# PDP8S.net
KiCad netlist of a schematic drawn in EAGLE
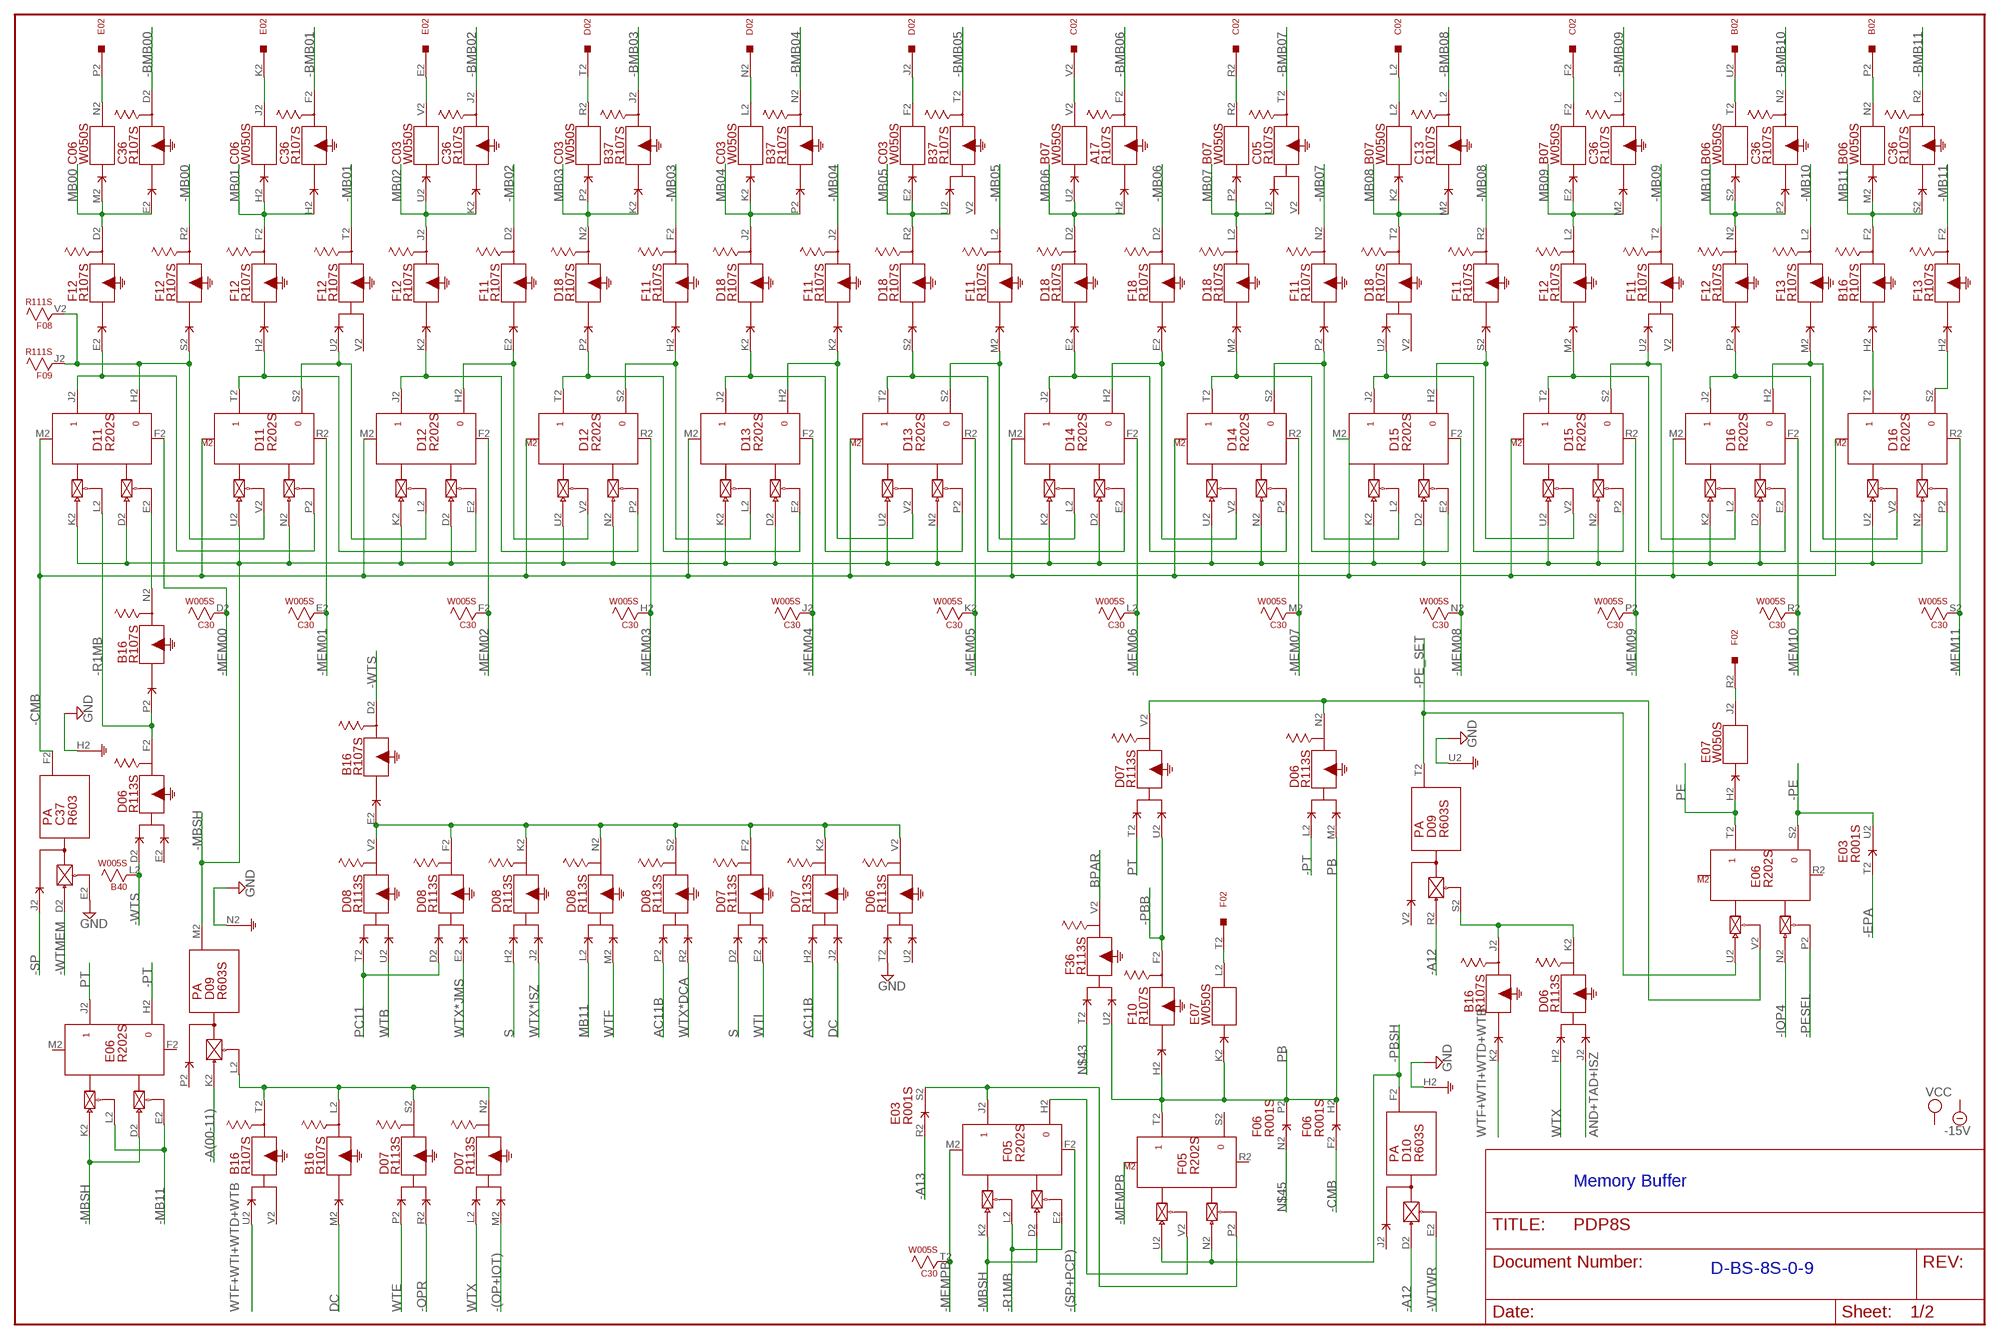
[diagram p0: schematic, sheet 1]
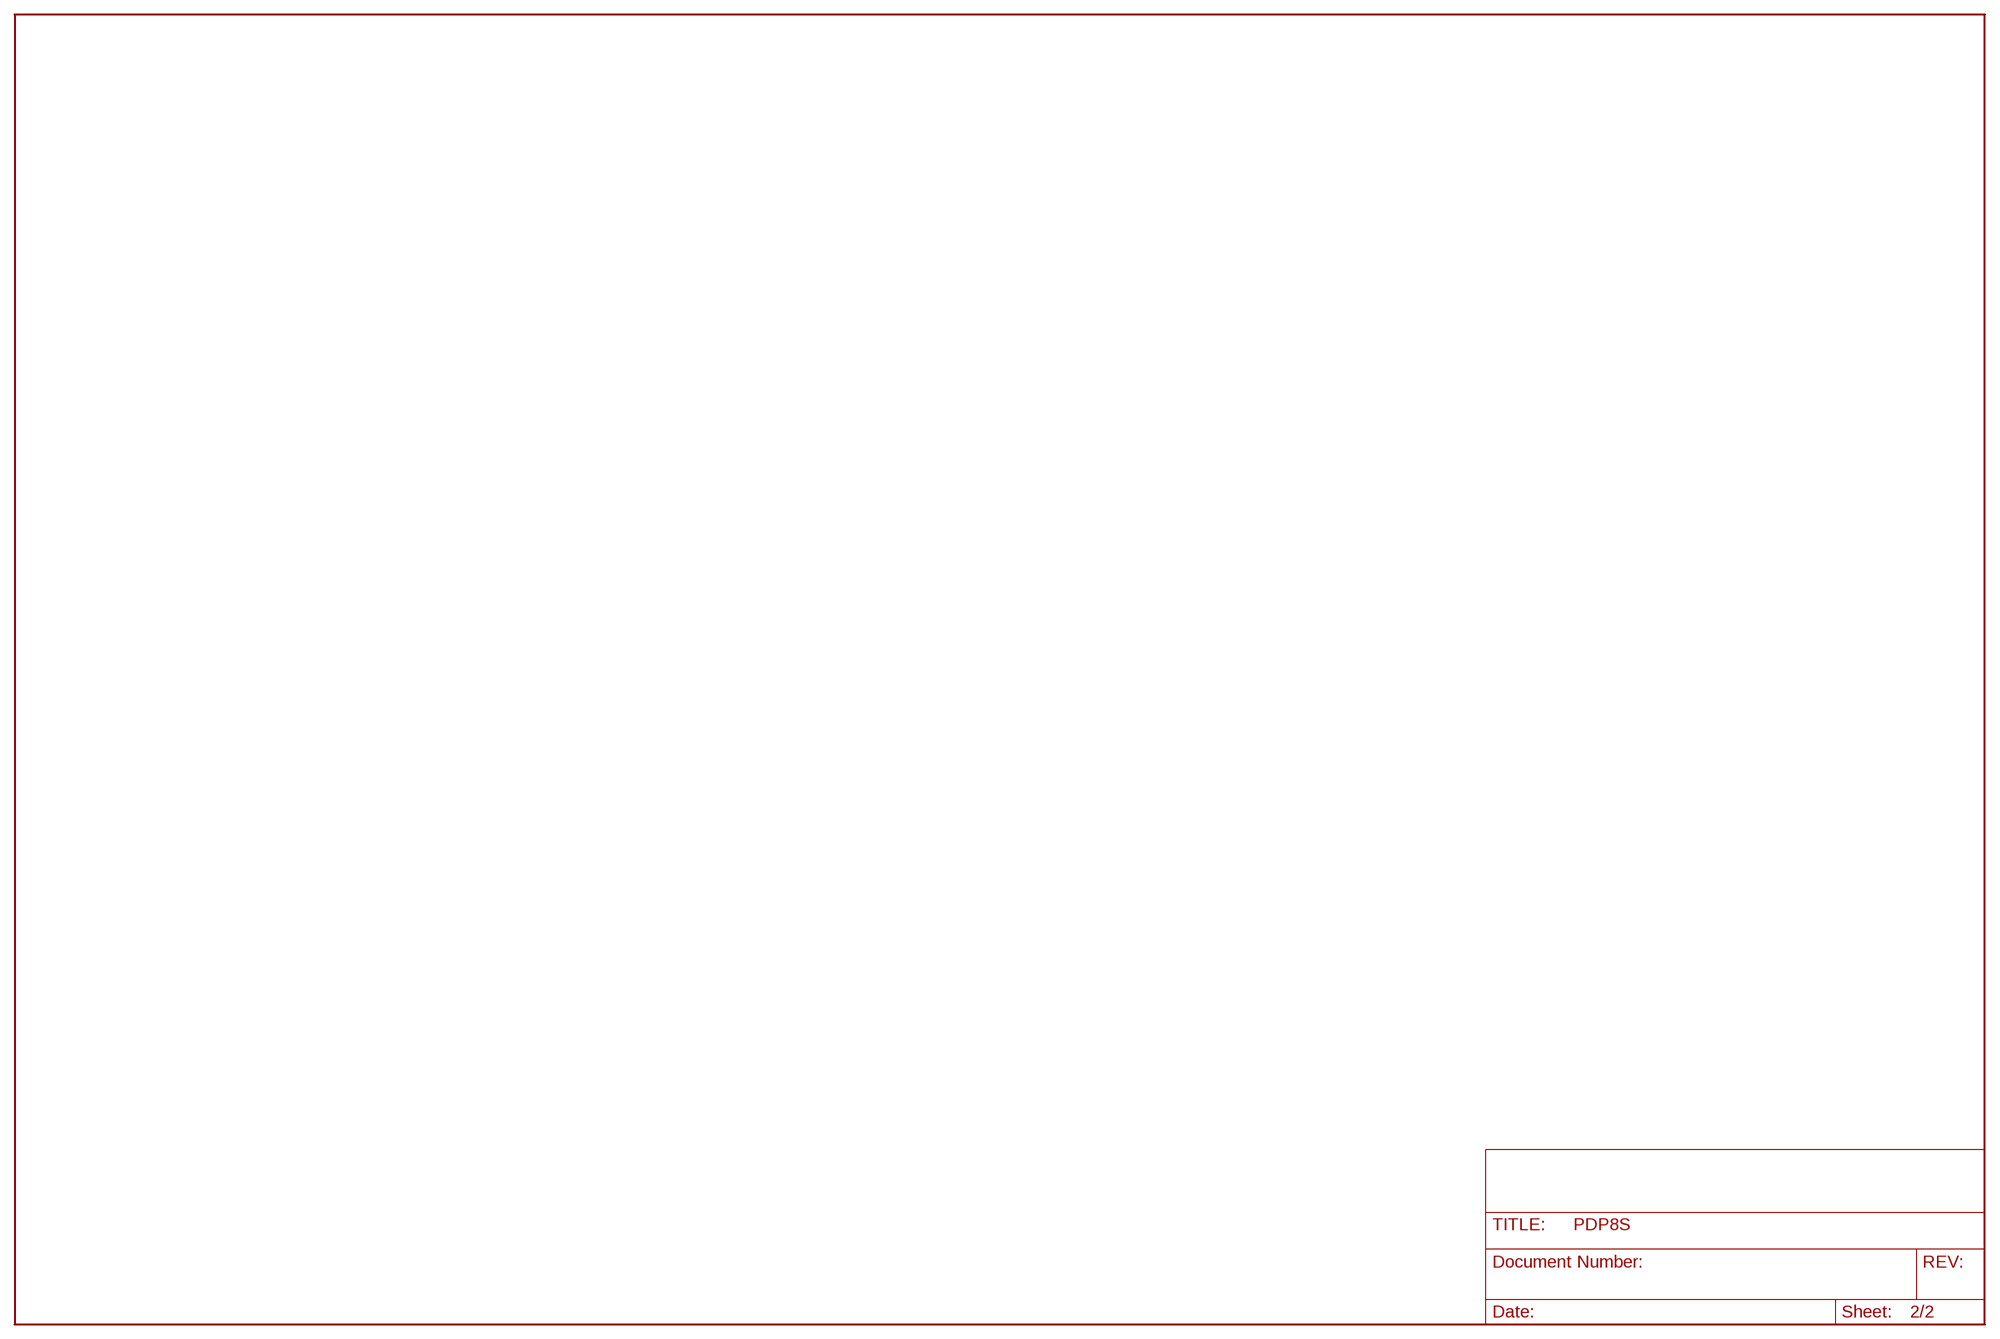
[diagram p1: schematic, sheet 2]

(export (version "E")
  (design (tool "Eeschema 10.0.6"))
  (components
    (comp (ref "A17")
      (value "R107S")
      (footprint "eagle-import:H807S")
      (libsource (lib "eagle-import") (part "R107S"))
    )
    (comp (ref "B02")
      (value "W023S")
      (footprint "eagle-import:H807S")
      (libsource (lib "eagle-import") (part "W023S"))
    )
    (comp (ref "B06")
      (value "W050S")
      (footprint "eagle-import:H807S")
      (libsource (lib "eagle-import") (part "W050S"))
    )
    (comp (ref "B07")
      (value "W050S")
      (footprint "eagle-import:H807S")
      (libsource (lib "eagle-import") (part "W050S"))
    )
    (comp (ref "B16")
      (value "R107S")
      (footprint "eagle-import:H807S")
      (libsource (lib "eagle-import") (part "R107S"))
    )
    (comp (ref "B37")
      (value "R107S")
      (footprint "eagle-import:H807S")
      (libsource (lib "eagle-import") (part "R107S"))
    )
    (comp (ref "B40")
      (value "W005S")
      (footprint "eagle-import:H807S")
      (libsource (lib "eagle-import") (part "W005S"))
    )
    (comp (ref "C02")
      (value "W023S")
      (footprint "eagle-import:H807S")
      (libsource (lib "eagle-import") (part "W023S"))
    )
    (comp (ref "C03")
      (value "W050S")
      (footprint "eagle-import:H807S")
      (libsource (lib "eagle-import") (part "W050S"))
    )
    (comp (ref "C05")
      (value "R107S")
      (footprint "eagle-import:H807S")
      (libsource (lib "eagle-import") (part "R107S"))
    )
    (comp (ref "C06")
      (value "W050S")
      (footprint "eagle-import:H807S")
      (libsource (lib "eagle-import") (part "W050S"))
    )
    (comp (ref "C13")
      (value "R107S")
      (footprint "eagle-import:H807S")
      (libsource (lib "eagle-import") (part "R107S"))
    )
    (comp (ref "C30")
      (value "W005S")
      (footprint "eagle-import:H807S")
      (libsource (lib "eagle-import") (part "W005S"))
    )
    (comp (ref "C36")
      (value "R107S")
      (footprint "eagle-import:H807S")
      (libsource (lib "eagle-import") (part "R107S"))
    )
    (comp (ref "C37")
      (value "R603")
      (footprint "eagle-import:H807")
      (libsource (lib "eagle-import") (part "R603"))
    )
    (comp (ref "D02")
      (value "W023S")
      (footprint "eagle-import:H807S")
      (libsource (lib "eagle-import") (part "W023S"))
    )
    (comp (ref "D06")
      (value "R113S")
      (footprint "eagle-import:H807S")
      (libsource (lib "eagle-import") (part "R113S"))
    )
    (comp (ref "D07")
      (value "R113S")
      (footprint "eagle-import:H807S")
      (libsource (lib "eagle-import") (part "R113S"))
    )
    (comp (ref "D08")
      (value "R113S")
      (footprint "eagle-import:H807S")
      (libsource (lib "eagle-import") (part "R113S"))
    )
    (comp (ref "D09")
      (value "R603S")
      (footprint "eagle-import:H807S")
      (libsource (lib "eagle-import") (part "R603S"))
    )
    (comp (ref "D10")
      (value "R603S")
      (footprint "eagle-import:H807S")
      (libsource (lib "eagle-import") (part "R603S"))
    )
    (comp (ref "D11")
      (value "R202S")
      (footprint "eagle-import:H807S")
      (libsource (lib "eagle-import") (part "R202S"))
    )
    (comp (ref "D12")
      (value "R202S")
      (footprint "eagle-import:H807S")
      (libsource (lib "eagle-import") (part "R202S"))
    )
    (comp (ref "D13")
      (value "R202S")
      (footprint "eagle-import:H807S")
      (libsource (lib "eagle-import") (part "R202S"))
    )
    (comp (ref "D14")
      (value "R202S")
      (footprint "eagle-import:H807S")
      (libsource (lib "eagle-import") (part "R202S"))
    )
    (comp (ref "D15")
      (value "R202S")
      (footprint "eagle-import:H807S")
      (libsource (lib "eagle-import") (part "R202S"))
    )
    (comp (ref "D16")
      (value "R202S")
      (footprint "eagle-import:H807S")
      (libsource (lib "eagle-import") (part "R202S"))
    )
    (comp (ref "D18")
      (value "R107S")
      (footprint "eagle-import:H807S")
      (libsource (lib "eagle-import") (part "R107S"))
    )
    (comp (ref "E02")
      (value "W023S")
      (footprint "eagle-import:H807S")
      (libsource (lib "eagle-import") (part "W023S"))
    )
    (comp (ref "E03")
      (value "R001S")
      (footprint "eagle-import:H807S")
      (libsource (lib "eagle-import") (part "R001S"))
    )
    (comp (ref "E06")
      (value "R202S")
      (footprint "eagle-import:H807S")
      (libsource (lib "eagle-import") (part "R202S"))
    )
    (comp (ref "E07")
      (value "W050S")
      (footprint "eagle-import:H807S")
      (libsource (lib "eagle-import") (part "W050S"))
    )
    (comp (ref "F02")
      (value "W023S")
      (footprint "eagle-import:H807S")
      (libsource (lib "eagle-import") (part "W023S"))
    )
    (comp (ref "F05")
      (value "R202S")
      (footprint "eagle-import:H807S")
      (libsource (lib "eagle-import") (part "R202S"))
    )
    (comp (ref "F06")
      (value "R001S")
      (footprint "eagle-import:H807S")
      (libsource (lib "eagle-import") (part "R001S"))
    )
    (comp (ref "F08")
      (value "R111S")
      (footprint "eagle-import:H807S")
      (libsource (lib "eagle-import") (part "R111S"))
    )
    (comp (ref "F09")
      (value "R111S")
      (footprint "eagle-import:H807S")
      (libsource (lib "eagle-import") (part "R111S"))
    )
    (comp (ref "F10")
      (value "R107S")
      (footprint "eagle-import:H807S")
      (libsource (lib "eagle-import") (part "R107S"))
    )
    (comp (ref "F11")
      (value "R107S")
      (footprint "eagle-import:H807S")
      (libsource (lib "eagle-import") (part "R107S"))
    )
    (comp (ref "F12")
      (value "R107S")
      (footprint "eagle-import:H807S")
      (libsource (lib "eagle-import") (part "R107S"))
    )
    (comp (ref "F13")
      (value "R107S")
      (footprint "eagle-import:H807S")
      (libsource (lib "eagle-import") (part "R107S"))
    )
    (comp (ref "F18")
      (value "R107S")
      (footprint "eagle-import:H807S")
      (libsource (lib "eagle-import") (part "R107S"))
    )
    (comp (ref "F36")
      (value "R113S")
      (footprint "eagle-import:H807S")
      (libsource (lib "eagle-import") (part "R113S"))
    )
  )
  (nets
    (net (code "1") (name "-(OP+IOT)") (class "Default")
      (node (ref "D07") (pin "M2") (pinfunction "I$2_M2") (pintype "input"))
    )
    (net (code "2") (name "-(SP+PCP)") (class "Default")
      (node (ref "F05") (pin "F2") (pinfunction "RESET_F2") (pintype "input"))
    )
    (net (code "4") (name "-A(00-11)") (class "Default")
      (node (ref "D09") (pin "K2") (pinfunction "PU0_K2") (pintype "input"))
    )
    (net (code "5") (name "-A12") (class "Default")
      (node (ref "D09") (pin "R2") (pinfunction "PU0_R2") (pintype "input"))
      (node (ref "D10") (pin "D2") (pinfunction "PU0_D2") (pintype "input"))
    )
    (net (code "6") (name "-A13") (class "Default")
      (node (ref "E03") (pin "R2") (pinfunction "D_R2") (pintype "input"))
    )
    (net (code "7") (name "-BMB00") (class "Default")
      (node (ref "C36") (pin "D2") (pinfunction "O$1_D2") (pintype "open_collector"))
    )
    (net (code "8") (name "-BMB01") (class "Default")
      (node (ref "C36") (pin "F2") (pinfunction "O$1_F2") (pintype "open_collector"))
    )
    (net (code "9") (name "-BMB02") (class "Default")
      (node (ref "C36") (pin "J2") (pinfunction "O$1_J2") (pintype "open_collector"))
    )
    (net (code "10") (name "-BMB03") (class "Default")
      (node (ref "B37") (pin "J2") (pinfunction "O$1_J2") (pintype "open_collector"))
    )
    (net (code "11") (name "-BMB04") (class "Default")
      (node (ref "B37") (pin "N2") (pinfunction "O$1_N2") (pintype "open_collector"))
    )
    (net (code "12") (name "-BMB05") (class "Default")
      (node (ref "B37") (pin "T2") (pinfunction "O$1_T2") (pintype "open_collector"))
    )
    (net (code "13") (name "-BMB06") (class "Default")
      (node (ref "A17") (pin "F2") (pinfunction "O$1_F2") (pintype "open_collector"))
    )
    (net (code "14") (name "-BMB07") (class "Default")
      (node (ref "C05") (pin "T2") (pinfunction "O$1_T2") (pintype "open_collector"))
    )
    (net (code "15") (name "-BMB08") (class "Default")
      (node (ref "C13") (pin "L2") (pinfunction "O$1_L2") (pintype "open_collector"))
    )
    (net (code "16") (name "-BMB09") (class "Default")
      (node (ref "C36") (pin "L2") (pinfunction "O$1_L2") (pintype "open_collector"))
    )
    (net (code "17") (name "-BMB10") (class "Default")
      (node (ref "C36") (pin "N2") (pinfunction "O$1_N2") (pintype "open_collector"))
    )
    (net (code "18") (name "-BMB11") (class "Default")
      (node (ref "C36") (pin "R2") (pinfunction "O$1_R2") (pintype "open_collector"))
    )
    (net (code "19") (name "-CMB") (class "Default")
      (node (ref "C37") (pin "F2") (pinfunction "O_F2") (pintype "open_collector"))
      (node (ref "D11") (pin "M2") (pinfunction "SET_M2") (pintype "passive"))
      (node (ref "D12") (pin "M2") (pinfunction "SET_M2") (pintype "passive"))
      (node (ref "D13") (pin "M2") (pinfunction "SET_M2") (pintype "passive"))
      (node (ref "D14") (pin "M2") (pinfunction "SET_M2") (pintype "passive"))
      (node (ref "D15") (pin "M2") (pinfunction "SET_M2") (pintype "passive"))
      (node (ref "D16") (pin "M2") (pinfunction "SET_M2") (pintype "passive"))
      (node (ref "F06") (pin "F2") (pinfunction "D_F2") (pintype "input"))
    )
    (net (code "20") (name "-EPA") (class "Default")
      (node (ref "E03") (pin "T2") (pinfunction "D_T2") (pintype "input"))
    )
    (net (code "21") (name "-IOP4") (class "Default")
      (node (ref "E06") (pin "N2") (pinfunction "PU0_N2") (pintype "input"))
    )
    (net (code "22") (name "-MB00") (class "Default")
      (node (ref "F12") (pin "R2") (pinfunction "O$1_R2") (pintype "open_collector"))
    )
    (net (code "23") (name "-MB01") (class "Default")
      (node (ref "F12") (pin "T2") (pinfunction "O$1_T2") (pintype "open_collector"))
    )
    (net (code "24") (name "-MB02") (class "Default")
      (node (ref "F11") (pin "D2") (pinfunction "O$1_D2") (pintype "open_collector"))
    )
    (net (code "25") (name "-MB03") (class "Default")
      (node (ref "F11") (pin "F2") (pinfunction "O$1_F2") (pintype "open_collector"))
    )
    (net (code "26") (name "-MB04") (class "Default")
      (node (ref "F11") (pin "J2") (pinfunction "O$1_J2") (pintype "open_collector"))
    )
    (net (code "27") (name "-MB05") (class "Default")
      (node (ref "F11") (pin "L2") (pinfunction "O$1_L2") (pintype "open_collector"))
    )
    (net (code "28") (name "-MB06") (class "Default")
      (node (ref "F18") (pin "D2") (pinfunction "O$1_D2") (pintype "open_collector"))
    )
    (net (code "29") (name "-MB07") (class "Default")
      (node (ref "F11") (pin "N2") (pinfunction "O$1_N2") (pintype "open_collector"))
    )
    (net (code "30") (name "-MB08") (class "Default")
      (node (ref "F11") (pin "R2") (pinfunction "O$1_R2") (pintype "open_collector"))
    )
    (net (code "31") (name "-MB09") (class "Default")
      (node (ref "F11") (pin "T2") (pinfunction "O$1_T2") (pintype "open_collector"))
    )
    (net (code "32") (name "-MB10") (class "Default")
      (node (ref "F13") (pin "L2") (pinfunction "O$1_L2") (pintype "open_collector"))
    )
    (net (code "33") (name "-MB11") (class "Default")
      (node (ref "E06") (pin "E2") (pinfunction "EN0_E2") (pintype "input"))
      (node (ref "E06") (pin "L2") (pinfunction "EN1_L2") (pintype "input"))
      (node (ref "F13") (pin "F2") (pinfunction "O$1_F2") (pintype "open_collector"))
    )
    (net (code "34") (name "-MBSH") (class "Default")
      (node (ref "D09") (pin "M2") (pinfunction "O_M2") (pintype "open_collector"))
      (node (ref "D11") (pin "D2") (pinfunction "PU0_D2") (pintype "input"))
      (node (ref "D11") (pin "K2") (pinfunction "PU1_K2") (pintype "input"))
      (node (ref "D11") (pin "N2") (pinfunction "PU0_N2") (pintype "input"))
      (node (ref "D11") (pin "U2") (pinfunction "PU1_U2") (pintype "input"))
      (node (ref "D12") (pin "D2") (pinfunction "PU0_D2") (pintype "input"))
      (node (ref "D12") (pin "K2") (pinfunction "PU1_K2") (pintype "input"))
      (node (ref "D12") (pin "N2") (pinfunction "PU0_N2") (pintype "input"))
      (node (ref "D12") (pin "U2") (pinfunction "PU1_U2") (pintype "input"))
      (node (ref "D13") (pin "D2") (pinfunction "PU0_D2") (pintype "input"))
      (node (ref "D13") (pin "K2") (pinfunction "PU1_K2") (pintype "input"))
      (node (ref "D13") (pin "N2") (pinfunction "PU0_N2") (pintype "input"))
      (node (ref "D13") (pin "U2") (pinfunction "PU1_U2") (pintype "input"))
      (node (ref "D14") (pin "D2") (pinfunction "PU0_D2") (pintype "input"))
      (node (ref "D14") (pin "K2") (pinfunction "PU1_K2") (pintype "input"))
      (node (ref "D14") (pin "N2") (pinfunction "PU0_N2") (pintype "input"))
      (node (ref "D14") (pin "U2") (pinfunction "PU1_U2") (pintype "input"))
      (node (ref "D15") (pin "D2") (pinfunction "PU0_D2") (pintype "input"))
      (node (ref "D15") (pin "K2") (pinfunction "PU1_K2") (pintype "input"))
      (node (ref "D15") (pin "N2") (pinfunction "PU0_N2") (pintype "input"))
      (node (ref "D15") (pin "U2") (pinfunction "PU1_U2") (pintype "input"))
      (node (ref "D16") (pin "D2") (pinfunction "PU0_D2") (pintype "input"))
      (node (ref "D16") (pin "K2") (pinfunction "PU1_K2") (pintype "input"))
      (node (ref "D16") (pin "N2") (pinfunction "PU0_N2") (pintype "input"))
      (node (ref "D16") (pin "U2") (pinfunction "PU1_U2") (pintype "input"))
      (node (ref "E06") (pin "D2") (pinfunction "PU0_D2") (pintype "input"))
      (node (ref "E06") (pin "K2") (pinfunction "PU1_K2") (pintype "input"))
      (node (ref "F05") (pin "D2") (pinfunction "PU0_D2") (pintype "input"))
      (node (ref "F05") (pin "K2") (pinfunction "PU1_K2") (pintype "input"))
    )
    (net (code "35") (name "-MEM00") (class "Default")
      (node (ref "C30") (pin "D2") (pinfunction "P$1_D2") (pintype "passive"))
      (node (ref "D11") (pin "F2") (pinfunction "RESET_F2") (pintype "input"))
    )
    (net (code "36") (name "-MEM01") (class "Default")
      (node (ref "C30") (pin "E2") (pinfunction "P$1_E2") (pintype "passive"))
      (node (ref "D11") (pin "R2") (pinfunction "RESET_R2") (pintype "input"))
    )
    (net (code "37") (name "-MEM02") (class "Default")
      (node (ref "C30") (pin "F2") (pinfunction "P$1_F2") (pintype "passive"))
      (node (ref "D12") (pin "F2") (pinfunction "RESET_F2") (pintype "input"))
    )
    (net (code "38") (name "-MEM03") (class "Default")
      (node (ref "C30") (pin "H2") (pinfunction "P$1_H2") (pintype "passive"))
      (node (ref "D12") (pin "R2") (pinfunction "RESET_R2") (pintype "input"))
    )
    (net (code "39") (name "-MEM04") (class "Default")
      (node (ref "C30") (pin "J2") (pinfunction "P$1_J2") (pintype "passive"))
      (node (ref "D13") (pin "F2") (pinfunction "RESET_F2") (pintype "input"))
    )
    (net (code "40") (name "-MEM05") (class "Default")
      (node (ref "C30") (pin "K2") (pinfunction "P$1_K2") (pintype "passive"))
      (node (ref "D13") (pin "R2") (pinfunction "RESET_R2") (pintype "input"))
    )
    (net (code "41") (name "-MEM06") (class "Default")
      (node (ref "C30") (pin "L2") (pinfunction "P$1_L2") (pintype "passive"))
      (node (ref "D14") (pin "F2") (pinfunction "RESET_F2") (pintype "input"))
    )
    (net (code "42") (name "-MEM07") (class "Default")
      (node (ref "C30") (pin "M2") (pinfunction "P$1_M2") (pintype "passive"))
      (node (ref "D14") (pin "R2") (pinfunction "RESET_R2") (pintype "input"))
    )
    (net (code "43") (name "-MEM08") (class "Default")
      (node (ref "C30") (pin "N2") (pinfunction "P$1_N2") (pintype "passive"))
      (node (ref "D15") (pin "F2") (pinfunction "RESET_F2") (pintype "input"))
    )
    (net (code "44") (name "-MEM09") (class "Default")
      (node (ref "C30") (pin "P2") (pinfunction "P$1_P2") (pintype "passive"))
      (node (ref "D15") (pin "R2") (pinfunction "RESET_R2") (pintype "input"))
    )
    (net (code "45") (name "-MEM10") (class "Default")
      (node (ref "C30") (pin "R2") (pinfunction "P$1_R2") (pintype "passive"))
      (node (ref "D16") (pin "F2") (pinfunction "RESET_F2") (pintype "input"))
    )
    (net (code "46") (name "-MEM11") (class "Default")
      (node (ref "C30") (pin "S2") (pinfunction "P$1_S2") (pintype "passive"))
      (node (ref "D16") (pin "R2") (pinfunction "RESET_R2") (pintype "input"))
    )
    (net (code "47") (name "-MEMPB") (class "Default")
      (node (ref "C30") (pin "T2") (pinfunction "P$1_T2") (pintype "passive"))
      (node (ref "F05") (pin "M2") (pinfunction "SET_M2") (pintype "passive"))
    )
    (net (code "48") (name "-OPR") (class "Default")
      (node (ref "D07") (pin "R2") (pinfunction "I$2_R2") (pintype "input"))
    )
    (net (code "49") (name "-PBB") (class "Default")
      (node (ref "D07") (pin "U2") (pinfunction "I$2_U2") (pintype "input"))
      (node (ref "F10") (pin "F2") (pinfunction "O$1_F2") (pintype "open_collector"))
    )
    (net (code "50") (name "-PBSH") (class "Default")
      (node (ref "D10") (pin "F2") (pinfunction "O_F2") (pintype "open_collector"))
      (node (ref "F05") (pin "N2") (pinfunction "PU0_N2") (pintype "input"))
      (node (ref "F05") (pin "U2") (pinfunction "PU1_U2") (pintype "input"))
    )
    (net (code "51") (name "-PE") (class "Default")
      (node (ref "E03") (pin "U2") (pinfunction "E_U2") (pintype "open_collector"))
      (node (ref "E06") (pin "S2") (pinfunction "0_S2") (pintype "open_collector"))
    )
    (net (code "52") (name "-PESEL") (class "Default")
      (node (ref "E06") (pin "P2") (pinfunction "EN0_P2") (pintype "input"))
    )
    (net (code "53") (name "-PE_SET") (class "Default")
      (node (ref "D09") (pin "T2") (pinfunction "O_T2") (pintype "open_collector"))
      (node (ref "E06") (pin "U2") (pinfunction "PU1_U2") (pintype "input"))
    )
    (net (code "54") (name "-PT") (class "Default")
      (node (ref "D06") (pin "L2") (pinfunction "I$1_L2") (pintype "input"))
      (node (ref "E06") (pin "H2") (pinfunction "0_H2") (pintype "open_collector"))
    )
    (net (code "55") (name "-R1MB") (class "Default")
      (node (ref "B16") (pin "P2") (pinfunction "I$1_P2") (pintype "input"))
      (node (ref "D06") (pin "F2") (pinfunction "O$1_F2") (pintype "open_collector"))
      (node (ref "D11") (pin "L2") (pinfunction "EN1_L2") (pintype "input"))
      (node (ref "F05") (pin "E2") (pinfunction "EN0_E2") (pintype "input"))
      (node (ref "F05") (pin "L2") (pinfunction "EN1_L2") (pintype "input"))
    )
    (net (code "56") (name "-SP") (class "Default")
      (node (ref "C37") (pin "J2") (pinfunction "I$1_J2") (pintype "passive"))
    )
    (net (code "57") (name "-WTMEM") (class "Default")
      (node (ref "C37") (pin "D2") (pinfunction "PU0_D2") (pintype "input"))
    )
    (net (code "58") (name "-WTS") (class "Default")
      (node (ref "B16") (pin "D2") (pinfunction "O$1_D2") (pintype "open_collector"))
      (node (ref "B40") (pin "L2") (pinfunction "P$1_L2") (pintype "passive"))
      (node (ref "D06") (pin "D2") (pinfunction "I$1_D2") (pintype "input"))
    )
    (net (code "59") (name "-WTWR") (class "Default")
      (node (ref "D10") (pin "E2") (pinfunction "EN0_E2") (pintype "passive"))
    )
    (net (code "60") (name "AC11B") (class "Default")
      (node (ref "D07") (pin "H2") (pinfunction "I$1_H2") (pintype "input"))
      (node (ref "D08") (pin "P2") (pinfunction "I$1_P2") (pintype "input"))
    )
    (net (code "61") (name "AND+TAD+ISZ") (class "Default")
      (node (ref "D06") (pin "J2") (pinfunction "I$2_J2") (pintype "input"))
    )
    (net (code "62") (name "BPAR") (class "Default")
      (node (ref "F36") (pin "V2") (pinfunction "O$1_V2") (pintype "open_collector"))
    )
    (net (code "63") (name "DC") (class "Default")
      (node (ref "B16") (pin "M2") (pinfunction "I$1_M2") (pintype "input"))
      (node (ref "D07") (pin "J2") (pinfunction "I$2_J2") (pintype "input"))
    )
    (net (code "64") (name "GND") (class "Default")
      (node (ref "C37") (pin "E2") (pinfunction "EN0_E2") (pintype "passive"))
      (node (ref "C37") (pin "H2") (pinfunction "G_H2") (pintype "input"))
      (node (ref "D06") (pin "T2") (pinfunction "I$1_T2") (pintype "input"))
      (node (ref "D09") (pin "N2") (pinfunction "G_N2") (pintype "input"))
      (node (ref "D09") (pin "U2") (pinfunction "G_U2") (pintype "input"))
      (node (ref "D10") (pin "H2") (pinfunction "G_H2") (pintype "input"))
    )
    (net (code "65") (name "MB00") (class "Default")
      (node (ref "C06") (pin "M2") (pinfunction "I$1_M2") (pintype "input"))
      (node (ref "C36") (pin "E2") (pinfunction "I$1_E2") (pintype "input"))
      (node (ref "F12") (pin "D2") (pinfunction "O$1_D2") (pintype "open_collector"))
    )
    (net (code "66") (name "MB01") (class "Default")
      (node (ref "C06") (pin "H2") (pinfunction "I$1_H2") (pintype "input"))
      (node (ref "C36") (pin "H2") (pinfunction "I$1_H2") (pintype "input"))
      (node (ref "F12") (pin "F2") (pinfunction "O$1_F2") (pintype "open_collector"))
    )
    (net (code "67") (name "MB02") (class "Default")
      (node (ref "C03") (pin "U2") (pinfunction "I$1_U2") (pintype "input"))
      (node (ref "C36") (pin "K2") (pinfunction "I$1_K2") (pintype "input"))
      (node (ref "F12") (pin "J2") (pinfunction "O$1_J2") (pintype "open_collector"))
    )
    (net (code "68") (name "MB03") (class "Default")
      (node (ref "B37") (pin "K2") (pinfunction "I$1_K2") (pintype "input"))
      (node (ref "C03") (pin "P2") (pinfunction "I$1_P2") (pintype "input"))
      (node (ref "D18") (pin "N2") (pinfunction "O$1_N2") (pintype "open_collector"))
    )
    (net (code "69") (name "MB04") (class "Default")
      (node (ref "B37") (pin "P2") (pinfunction "I$1_P2") (pintype "input"))
      (node (ref "C03") (pin "K2") (pinfunction "I$1_K2") (pintype "input"))
      (node (ref "D18") (pin "J2") (pinfunction "O$1_J2") (pintype "open_collector"))
    )
    (net (code "70") (name "MB05") (class "Default")
      (node (ref "B37") (pin "U2") (pinfunction "I$1_U2") (pintype "input"))
      (node (ref "C03") (pin "E2") (pinfunction "I$1_E2") (pintype "input"))
      (node (ref "D18") (pin "R2") (pinfunction "O$1_R2") (pintype "open_collector"))
    )
    (net (code "71") (name "MB06") (class "Default")
      (node (ref "A17") (pin "H2") (pinfunction "I$1_H2") (pintype "input"))
      (node (ref "B07") (pin "U2") (pinfunction "I$1_U2") (pintype "input"))
      (node (ref "D18") (pin "D2") (pinfunction "O$1_D2") (pintype "open_collector"))
    )
    (net (code "72") (name "MB07") (class "Default")
      (node (ref "B07") (pin "P2") (pinfunction "I$1_P2") (pintype "input"))
      (node (ref "C05") (pin "U2") (pinfunction "I$1_U2") (pintype "input"))
      (node (ref "D18") (pin "L2") (pinfunction "O$1_L2") (pintype "open_collector"))
    )
    (net (code "73") (name "MB08") (class "Default")
      (node (ref "B07") (pin "K2") (pinfunction "I$1_K2") (pintype "input"))
      (node (ref "C13") (pin "M2") (pinfunction "I$1_M2") (pintype "input"))
      (node (ref "D18") (pin "T2") (pinfunction "O$1_T2") (pintype "open_collector"))
    )
    (net (code "74") (name "MB09") (class "Default")
      (node (ref "B07") (pin "E2") (pinfunction "I$1_E2") (pintype "input"))
      (node (ref "C36") (pin "M2") (pinfunction "I$1_M2") (pintype "input"))
      (node (ref "F12") (pin "L2") (pinfunction "O$1_L2") (pintype "open_collector"))
    )
    (net (code "75") (name "MB10") (class "Default")
      (node (ref "B06") (pin "S2") (pinfunction "I$1_S2") (pintype "input"))
      (node (ref "C36") (pin "P2") (pinfunction "I$1_P2") (pintype "input"))
      (node (ref "F12") (pin "N2") (pinfunction "O$1_N2") (pintype "open_collector"))
    )
    (net (code "76") (name "MB11") (class "Default")
      (node (ref "B06") (pin "M2") (pinfunction "I$1_M2") (pintype "input"))
      (node (ref "B16") (pin "F2") (pinfunction "O$1_F2") (pintype "open_collector"))
      (node (ref "C36") (pin "S2") (pinfunction "I$1_S2") (pintype "input"))
      (node (ref "D08") (pin "L2") (pinfunction "I$1_L2") (pintype "input"))
    )
    (net (code "77") (name "N$43") (class "Default")
      (node (ref "F36") (pin "T2") (pinfunction "I$1_T2") (pintype "input"))
    )
    (net (code "78") (name "N$45") (class "Default")
      (node (ref "F06") (pin "N2") (pinfunction "D_N2") (pintype "input"))
    )
    (net (code "79") (name "Net-(B02M-P$2)") (class "Default")
      (node (ref "B02") (pin "P2") (pinfunction "P$2_P2") (pintype "bidirectional"))
      (node (ref "B06") (pin "N2") (pinfunction "O$1_N2") (pintype "output"))
    )
    (net (code "80") (name "Net-(B02Q-P$2)") (class "Default")
      (node (ref "B02") (pin "U2") (pinfunction "P$2_U2") (pintype "bidirectional"))
      (node (ref "B06") (pin "T2") (pinfunction "O$1_T2") (pintype "output"))
    )
    (net (code "81") (name "Net-(B07A-O$1)") (class "Default")
      (node (ref "B07") (pin "F2") (pinfunction "O$1_F2") (pintype "output"))
      (node (ref "C02") (pin "F2") (pinfunction "P$2_F2") (pintype "bidirectional"))
    )
    (net (code "82") (name "Net-(B07E-O$1)") (class "Default")
      (node (ref "B07") (pin "L2") (pinfunction "O$1_L2") (pintype "output"))
      (node (ref "C02") (pin "L2") (pinfunction "P$2_L2") (pintype "bidirectional"))
    )
    (net (code "83") (name "Net-(B07G-O$1)") (class "Default")
      (node (ref "B07") (pin "R2") (pinfunction "O$1_R2") (pintype "output"))
      (node (ref "C02") (pin "R2") (pinfunction "P$2_R2") (pintype "bidirectional"))
    )
    (net (code "84") (name "Net-(B07I-O$1)") (class "Default")
      (node (ref "B07") (pin "V2") (pinfunction "O$1_V2") (pintype "output"))
      (node (ref "C02") (pin "V2") (pinfunction "P$2_V2") (pintype "bidirectional"))
    )
    (net (code "85") (name "Net-(B16A-I$1)") (class "Default")
      (node (ref "B16") (pin "E2") (pinfunction "I$1_E2") (pintype "input"))
      (node (ref "D06") (pin "V2") (pinfunction "O$1_V2") (pintype "open_collector"))
      (node (ref "D07") (pin "F2") (pinfunction "O$1_F2") (pintype "open_collector"))
      (node (ref "D07") (pin "K2") (pinfunction "O$1_K2") (pintype "open_collector"))
      (node (ref "D08") (pin "F2") (pinfunction "O$1_F2") (pintype "open_collector"))
      (node (ref "D08") (pin "K2") (pinfunction "O$1_K2") (pintype "open_collector"))
      (node (ref "D08") (pin "N2") (pinfunction "O$1_N2") (pintype "open_collector"))
      (node (ref "D08") (pin "S2") (pinfunction "O$1_S2") (pintype "open_collector"))
      (node (ref "D08") (pin "V2") (pinfunction "O$1_V2") (pintype "open_collector"))
    )
    (net (code "86") (name "Net-(B16B-I$1)") (class "Default")
      (node (ref "B16") (pin "H2") (pinfunction "I$1_H2") (pintype "input"))
      (node (ref "D16") (pin "T2") (pinfunction "1_T2") (pintype "open_collector"))
    )
    (net (code "87") (name "Net-(B16E-O$1)") (class "Default")
      (node (ref "B16") (pin "J2") (pinfunction "O$1_J2") (pintype "open_collector"))
      (node (ref "D06") (pin "K2") (pinfunction "O$1_K2") (pintype "open_collector"))
      (node (ref "D09") (pin "S2") (pinfunction "EN0_S2") (pintype "passive"))
    )
    (net (code "88") (name "Net-(B16F-O$1)") (class "Default")
      (node (ref "B16") (pin "L2") (pinfunction "O$1_L2") (pintype "open_collector"))
      (node (ref "B16") (pin "T2") (pinfunction "O$1_T2") (pintype "open_collector"))
      (node (ref "D07") (pin "N2") (pinfunction "O$1_N2") (pintype "open_collector"))
      (node (ref "D07") (pin "S2") (pinfunction "O$1_S2") (pintype "open_collector"))
      (node (ref "D09") (pin "L2") (pinfunction "EN0_L2") (pintype "passive"))
    )
    (net (code "89") (name "Net-(B16G-O$1)") (class "Default")
      (node (ref "B16") (pin "N2") (pinfunction "O$1_N2") (pintype "open_collector"))
      (node (ref "D11") (pin "E2") (pinfunction "EN0_E2") (pintype "input"))
    )
    (net (code "90") (name "Net-(C03A-O$1)") (class "Default")
      (node (ref "C03") (pin "F2") (pinfunction "O$1_F2") (pintype "output"))
      (node (ref "D02") (pin "J2") (pinfunction "P$2_J2") (pintype "bidirectional"))
    )
    (net (code "91") (name "Net-(C03E-O$1)") (class "Default")
      (node (ref "C03") (pin "L2") (pinfunction "O$1_L2") (pintype "output"))
      (node (ref "D02") (pin "N2") (pinfunction "P$2_N2") (pintype "bidirectional"))
    )
    (net (code "92") (name "Net-(C03G-O$1)") (class "Default")
      (node (ref "C03") (pin "R2") (pinfunction "O$1_R2") (pintype "output"))
      (node (ref "D02") (pin "T2") (pinfunction "P$2_T2") (pintype "bidirectional"))
    )
    (net (code "93") (name "Net-(C03I-O$1)") (class "Default")
      (node (ref "C03") (pin "V2") (pinfunction "O$1_V2") (pintype "output"))
      (node (ref "E02") (pin "E2") (pinfunction "P$2_E2") (pintype "bidirectional"))
    )
    (net (code "94") (name "Net-(C06D-O$1)") (class "Default")
      (node (ref "C06") (pin "J2") (pinfunction "O$1_J2") (pintype "output"))
      (node (ref "E02") (pin "K2") (pinfunction "P$2_K2") (pintype "bidirectional"))
    )
    (net (code "95") (name "Net-(C06F-O$1)") (class "Default")
      (node (ref "C06") (pin "N2") (pinfunction "O$1_N2") (pintype "output"))
      (node (ref "E02") (pin "P2") (pinfunction "P$2_P2") (pintype "bidirectional"))
    )
    (net (code "96") (name "Net-(D06E-O$1)") (class "Default")
      (node (ref "D06") (pin "N2") (pinfunction "O$1_N2") (pintype "open_collector"))
      (node (ref "D07") (pin "V2") (pinfunction "O$1_V2") (pintype "open_collector"))
      (node (ref "E06") (pin "V2") (pinfunction "EN1_V2") (pintype "input"))
    )
    (net (code "97") (name "Net-(D11C-0)") (class "Default")
      (node (ref "D11") (pin "H2") (pinfunction "0_H2") (pintype "open_collector"))
      (node (ref "D11") (pin "V2") (pinfunction "EN1_V2") (pintype "input"))
      (node (ref "F08") (pin "V2") (pinfunction "P$1_V2") (pintype "passive"))
      (node (ref "F09") (pin "J2") (pinfunction "P$1_J2") (pintype "passive"))
      (node (ref "F12") (pin "S2") (pinfunction "I$1_S2") (pintype "input"))
    )
    (net (code "98") (name "Net-(D11C-1)") (class "Default")
      (node (ref "D11") (pin "J2") (pinfunction "1_J2") (pintype "open_collector"))
      (node (ref "D11") (pin "P2") (pinfunction "EN0_P2") (pintype "input"))
      (node (ref "F12") (pin "E2") (pinfunction "I$1_E2") (pintype "input"))
    )
    (net (code "99") (name "Net-(D11D-0)") (class "Default")
      (node (ref "D11") (pin "S2") (pinfunction "0_S2") (pintype "open_collector"))
      (node (ref "D12") (pin "L2") (pinfunction "EN1_L2") (pintype "input"))
      (node (ref "F12") (pin "U2") (pinfunction "I$1_U2") (pintype "input"))
    )
    (net (code "100") (name "Net-(D11D-1)") (class "Default")
      (node (ref "D11") (pin "T2") (pinfunction "1_T2") (pintype "open_collector"))
      (node (ref "D12") (pin "E2") (pinfunction "EN0_E2") (pintype "input"))
      (node (ref "F12") (pin "H2") (pinfunction "I$1_H2") (pintype "input"))
    )
    (net (code "101") (name "Net-(D12C-0)") (class "Default")
      (node (ref "D12") (pin "H2") (pinfunction "0_H2") (pintype "open_collector"))
      (node (ref "D12") (pin "V2") (pinfunction "EN1_V2") (pintype "input"))
      (node (ref "F11") (pin "E2") (pinfunction "I$1_E2") (pintype "input"))
    )
    (net (code "102") (name "Net-(D12C-1)") (class "Default")
      (node (ref "D12") (pin "J2") (pinfunction "1_J2") (pintype "open_collector"))
      (node (ref "D12") (pin "P2") (pinfunction "EN0_P2") (pintype "input"))
      (node (ref "F12") (pin "K2") (pinfunction "I$1_K2") (pintype "input"))
    )
    (net (code "103") (name "Net-(D12D-0)") (class "Default")
      (node (ref "D12") (pin "S2") (pinfunction "0_S2") (pintype "open_collector"))
      (node (ref "D13") (pin "L2") (pinfunction "EN1_L2") (pintype "input"))
      (node (ref "F11") (pin "H2") (pinfunction "I$1_H2") (pintype "input"))
    )
    (net (code "104") (name "Net-(D12D-1)") (class "Default")
      (node (ref "D12") (pin "T2") (pinfunction "1_T2") (pintype "open_collector"))
      (node (ref "D13") (pin "E2") (pinfunction "EN0_E2") (pintype "input"))
      (node (ref "D18") (pin "P2") (pinfunction "I$1_P2") (pintype "input"))
    )
    (net (code "105") (name "Net-(D13C-0)") (class "Default")
      (node (ref "D13") (pin "H2") (pinfunction "0_H2") (pintype "open_collector"))
      (node (ref "D13") (pin "V2") (pinfunction "EN1_V2") (pintype "input"))
      (node (ref "F11") (pin "K2") (pinfunction "I$1_K2") (pintype "input"))
    )
    (net (code "106") (name "Net-(D13C-1)") (class "Default")
      (node (ref "D13") (pin "J2") (pinfunction "1_J2") (pintype "open_collector"))
      (node (ref "D13") (pin "P2") (pinfunction "EN0_P2") (pintype "input"))
      (node (ref "D18") (pin "K2") (pinfunction "I$1_K2") (pintype "input"))
    )
    (net (code "107") (name "Net-(D13D-0)") (class "Default")
      (node (ref "D13") (pin "S2") (pinfunction "0_S2") (pintype "open_collector"))
      (node (ref "D14") (pin "L2") (pinfunction "EN1_L2") (pintype "input"))
      (node (ref "F11") (pin "M2") (pinfunction "I$1_M2") (pintype "input"))
    )
    (net (code "108") (name "Net-(D13D-1)") (class "Default")
      (node (ref "D13") (pin "T2") (pinfunction "1_T2") (pintype "open_collector"))
      (node (ref "D14") (pin "E2") (pinfunction "EN0_E2") (pintype "input"))
      (node (ref "D18") (pin "S2") (pinfunction "I$1_S2") (pintype "input"))
    )
    (net (code "109") (name "Net-(D14C-0)") (class "Default")
      (node (ref "D14") (pin "H2") (pinfunction "0_H2") (pintype "open_collector"))
      (node (ref "D14") (pin "V2") (pinfunction "EN1_V2") (pintype "input"))
      (node (ref "F18") (pin "E2") (pinfunction "I$1_E2") (pintype "input"))
    )
    (net (code "110") (name "Net-(D14C-1)") (class "Default")
      (node (ref "D14") (pin "J2") (pinfunction "1_J2") (pintype "open_collector"))
      (node (ref "D14") (pin "P2") (pinfunction "EN0_P2") (pintype "input"))
      (node (ref "D18") (pin "E2") (pinfunction "I$1_E2") (pintype "input"))
    )
    (net (code "111") (name "Net-(D14D-0)") (class "Default")
      (node (ref "D14") (pin "S2") (pinfunction "0_S2") (pintype "open_collector"))
      (node (ref "D15") (pin "L2") (pinfunction "EN1_L2") (pintype "input"))
      (node (ref "F11") (pin "P2") (pinfunction "I$1_P2") (pintype "input"))
    )
    (net (code "112") (name "Net-(D14D-1)") (class "Default")
      (node (ref "D14") (pin "T2") (pinfunction "1_T2") (pintype "open_collector"))
      (node (ref "D15") (pin "E2") (pinfunction "EN0_E2") (pintype "input"))
      (node (ref "D18") (pin "M2") (pinfunction "I$1_M2") (pintype "input"))
    )
    (net (code "113") (name "Net-(D15C-0)") (class "Default")
      (node (ref "D15") (pin "H2") (pinfunction "0_H2") (pintype "open_collector"))
      (node (ref "D15") (pin "V2") (pinfunction "EN1_V2") (pintype "input"))
      (node (ref "F11") (pin "S2") (pinfunction "I$1_S2") (pintype "input"))
    )
    (net (code "114") (name "Net-(D15C-1)") (class "Default")
      (node (ref "D15") (pin "J2") (pinfunction "1_J2") (pintype "open_collector"))
      (node (ref "D15") (pin "P2") (pinfunction "EN0_P2") (pintype "input"))
      (node (ref "D18") (pin "U2") (pinfunction "I$1_U2") (pintype "input"))
    )
    (net (code "115") (name "Net-(D15D-0)") (class "Default")
      (node (ref "D15") (pin "S2") (pinfunction "0_S2") (pintype "open_collector"))
      (node (ref "D16") (pin "L2") (pinfunction "EN1_L2") (pintype "input"))
      (node (ref "F11") (pin "U2") (pinfunction "I$1_U2") (pintype "input"))
    )
    (net (code "116") (name "Net-(D15D-1)") (class "Default")
      (node (ref "D15") (pin "T2") (pinfunction "1_T2") (pintype "open_collector"))
      (node (ref "D16") (pin "E2") (pinfunction "EN0_E2") (pintype "input"))
      (node (ref "F12") (pin "M2") (pinfunction "I$1_M2") (pintype "input"))
    )
    (net (code "117") (name "Net-(D16C-0)") (class "Default")
      (node (ref "D16") (pin "H2") (pinfunction "0_H2") (pintype "open_collector"))
      (node (ref "D16") (pin "V2") (pinfunction "EN1_V2") (pintype "input"))
      (node (ref "F13") (pin "M2") (pinfunction "I$1_M2") (pintype "input"))
    )
    (net (code "118") (name "Net-(D16C-1)") (class "Default")
      (node (ref "D16") (pin "J2") (pinfunction "1_J2") (pintype "open_collector"))
      (node (ref "D16") (pin "P2") (pinfunction "EN0_P2") (pintype "input"))
      (node (ref "F12") (pin "P2") (pinfunction "I$1_P2") (pintype "input"))
    )
    (net (code "119") (name "Net-(D16D-0)") (class "Default")
      (node (ref "D16") (pin "S2") (pinfunction "0_S2") (pintype "open_collector"))
      (node (ref "F13") (pin "H2") (pinfunction "I$1_H2") (pintype "input"))
    )
    (net (code "120") (name "Net-(E03H-E)") (class "Default")
      (node (ref "E03") (pin "S2") (pinfunction "E_S2") (pintype "open_collector"))
      (node (ref "F05") (pin "J2") (pinfunction "1_J2") (pintype "open_collector"))
      (node (ref "F05") (pin "P2") (pinfunction "EN0_P2") (pintype "input"))
    )
    (net (code "121") (name "Net-(E07D-O$1)") (class "Default")
      (node (ref "E07") (pin "J2") (pinfunction "O$1_J2") (pintype "output"))
      (node (ref "F02") (pin "R2") (pinfunction "P$2_R2") (pintype "bidirectional"))
    )
    (net (code "122") (name "Net-(E07E-O$1)") (class "Default")
      (node (ref "E07") (pin "L2") (pinfunction "O$1_L2") (pintype "output"))
      (node (ref "F02") (pin "T2") (pinfunction "P$2_T2") (pintype "bidirectional"))
    )
    (net (code "123") (name "Net-(F05C-0)") (class "Default")
      (node (ref "F05") (pin "H2") (pinfunction "0_H2") (pintype "open_collector"))
      (node (ref "F05") (pin "V2") (pinfunction "EN1_V2") (pintype "input"))
    )
    (net (code "124") (name "PB") (class "Default")
      (node (ref "D06") (pin "M2") (pinfunction "I$2_M2") (pintype "input"))
      (node (ref "E07") (pin "K2") (pinfunction "I$1_K2") (pintype "input"))
      (node (ref "F05") (pin "T2") (pinfunction "1_T2") (pintype "open_collector"))
      (node (ref "F06") (pin "H2") (pinfunction "E_H2") (pintype "open_collector"))
      (node (ref "F06") (pin "P2") (pinfunction "E_P2") (pintype "open_collector"))
      (node (ref "F10") (pin "H2") (pinfunction "I$1_H2") (pintype "input"))
      (node (ref "F36") (pin "U2") (pinfunction "I$2_U2") (pintype "input"))
    )
    (net (code "125") (name "PC11") (class "Default")
      (node (ref "D08") (pin "D2") (pinfunction "I$1_D2") (pintype "input"))
      (node (ref "D08") (pin "T2") (pinfunction "I$1_T2") (pintype "input"))
    )
    (net (code "126") (name "PE") (class "Default")
      (node (ref "E06") (pin "T2") (pinfunction "1_T2") (pintype "open_collector"))
      (node (ref "E07") (pin "H2") (pinfunction "I$1_H2") (pintype "input"))
    )
    (net (code "127") (name "PT") (class "Default")
      (node (ref "D07") (pin "T2") (pinfunction "I$1_T2") (pintype "input"))
      (node (ref "E06") (pin "J2") (pinfunction "1_J2") (pintype "open_collector"))
    )
    (net (code "128") (name "S") (class "Default")
      (node (ref "D07") (pin "D2") (pinfunction "I$1_D2") (pintype "input"))
      (node (ref "D08") (pin "H2") (pinfunction "I$1_H2") (pintype "input"))
    )
    (net (code "130") (name "WTB") (class "Default")
      (node (ref "D08") (pin "U2") (pinfunction "I$2_U2") (pintype "input"))
    )
    (net (code "131") (name "WTE") (class "Default")
      (node (ref "D07") (pin "P2") (pinfunction "I$1_P2") (pintype "input"))
    )
    (net (code "132") (name "WTF") (class "Default")
      (node (ref "D08") (pin "M2") (pinfunction "I$2_M2") (pintype "input"))
    )
    (net (code "133") (name "WTF+WTI+WTD+WTB") (class "Default")
      (node (ref "B16") (pin "K2") (pinfunction "I$1_K2") (pintype "input"))
      (node (ref "B16") (pin "U2") (pinfunction "I$1_U2") (pintype "input"))
    )
    (net (code "134") (name "WTI") (class "Default")
      (node (ref "D07") (pin "E2") (pinfunction "I$2_E2") (pintype "input"))
    )
    (net (code "135") (name "WTX") (class "Default")
      (node (ref "D06") (pin "H2") (pinfunction "I$1_H2") (pintype "input"))
      (node (ref "D07") (pin "L2") (pinfunction "I$1_L2") (pintype "input"))
    )
    (net (code "136") (name "WTX*DCA") (class "Default")
      (node (ref "D08") (pin "R2") (pinfunction "I$2_R2") (pintype "input"))
    )
    (net (code "137") (name "WTX*ISZ") (class "Default")
      (node (ref "D08") (pin "J2") (pinfunction "I$2_J2") (pintype "input"))
    )
    (net (code "138") (name "WTX*JMS") (class "Default")
      (node (ref "D08") (pin "E2") (pinfunction "I$2_E2") (pintype "input"))
    )
    (net (code "139") (name "unconnected-(B16I-I$2-PadV2)") (class "Default")
      (node (ref "B16") (pin "V2") (pinfunction "I$2_V2") (pintype "passive"))
    )
    (net (code "140") (name "unconnected-(B37I-I$2-PadV2)") (class "Default")
      (node (ref "B37") (pin "V2") (pinfunction "I$2_V2") (pintype "passive"))
    )
    (net (code "141") (name "unconnected-(C05I-I$2-PadV2)") (class "Default")
      (node (ref "C05") (pin "V2") (pinfunction "I$2_V2") (pintype "passive"))
    )
    (net (code "142") (name "unconnected-(D06A-I$2-PadE2)") (class "Default")
      (node (ref "D06") (pin "E2") (pinfunction "I$2_E2") (pintype "input"))
    )
    (net (code "143") (name "unconnected-(D06G-I$2-PadU2)") (class "Default")
      (node (ref "D06") (pin "U2") (pinfunction "I$2_U2") (pintype "input"))
    )
    (net (code "144") (name "unconnected-(D09D-I$1-PadP2)") (class "Default")
      (node (ref "D09") (pin "P2") (pinfunction "I$1_P2") (pintype "passive"))
    )
    (net (code "145") (name "unconnected-(D09E-I$1-PadV2)") (class "Default")
      (node (ref "D09") (pin "V2") (pinfunction "I$1_V2") (pintype "passive"))
    )
    (net (code "146") (name "unconnected-(D10A-I$1-PadJ2)") (class "Default")
      (node (ref "D10") (pin "J2") (pinfunction "I$1_J2") (pintype "passive"))
    )
    (net (code "147") (name "unconnected-(D18I-I$2-PadV2)") (class "Default")
      (node (ref "D18") (pin "V2") (pinfunction "I$2_V2") (pintype "passive"))
    )
    (net (code "148") (name "unconnected-(E06C-RESET-PadF2)") (class "Default")
      (node (ref "E06") (pin "F2") (pinfunction "RESET_F2") (pintype "input"))
    )
    (net (code "149") (name "unconnected-(E06C-SET-PadM2)") (class "Default")
      (node (ref "E06") (pin "M2") (pinfunction "SET_M2") (pintype "passive"))
    )
    (net (code "150") (name "unconnected-(E06D-RESET-PadR2)") (class "Default")
      (node (ref "E06") (pin "R2") (pinfunction "RESET_R2") (pintype "input"))
    )
    (net (code "151") (name "unconnected-(F05D-0-PadS2)") (class "Default")
      (node (ref "F05") (pin "S2") (pinfunction "0_S2") (pintype "open_collector"))
    )
    (net (code "152") (name "unconnected-(F05D-RESET-PadR2)") (class "Default")
      (node (ref "F05") (pin "R2") (pinfunction "RESET_R2") (pintype "input"))
    )
    (net (code "153") (name "unconnected-(F11I-I$2-PadV2)") (class "Default")
      (node (ref "F11") (pin "V2") (pinfunction "I$2_V2") (pintype "passive"))
    )
    (net (code "154") (name "unconnected-(F12I-I$2-PadV2)") (class "Default")
      (node (ref "F12") (pin "V2") (pinfunction "I$2_V2") (pintype "passive"))
    )
  )
)
